# module.net
KiCad netlist of a schematic drawn in EAGLE
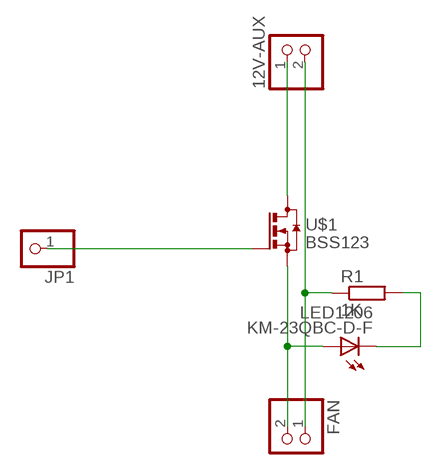
[diagram p0: schematic, sheet 1]

(export (version "E")
  (design (tool "Eeschema 10.0.6"))
  (components
    (comp (ref "12V-AUX")
      (value "PINHD-1X2")
      (footprint "eagle-import:1X02")
      (libsource (lib "eagle-import") (part "PINHD-1X2"))
    )
    (comp (ref "FAN")
      (value "PINHD-1X2")
      (footprint "eagle-import:1X02")
      (libsource (lib "eagle-import") (part "PINHD-1X2"))
    )
    (comp (ref "JP1")
      (value "PINHD-1X1")
      (footprint "eagle-import:1X01")
      (libsource (lib "eagle-import") (part "PINHD-1X1"))
    )
    (comp (ref "KM-23QBC-D-F")
      (value "LED1206")
      (footprint "eagle-import:LED1206")
      (libsource (lib "eagle-import") (part "LED1206"))
    )
    (comp (ref "R1")
      (value "1K")
      (footprint "eagle-import:R1206")
      (libsource (lib "eagle-import") (part "R-EU_R1206"))
    )
    (comp (ref "U$1")
      (value "BSS123")
      (footprint "eagle-import:SOT23")
      (libsource (lib "eagle-import") (part "BSS123"))
    )
  )
  (nets
    (net (code "1") (name "Net-(12V-AUX-Pad2)") (class "Default")
      (node (ref "12V-AUX") (pin "2") (pinfunction "2_2") (pintype "passive"))
      (node (ref "FAN") (pin "1") (pinfunction "1_1") (pintype "passive"))
      (node (ref "R1") (pin "1") (pinfunction "1_1") (pintype "passive"))
    )
    (net (code "2") (name "Net-(KM-23QBC-D-F-PadC)") (class "Default")
      (node (ref "KM-23QBC-D-F") (pin "C") (pinfunction "C_C") (pintype "passive"))
      (node (ref "R1") (pin "2") (pinfunction "2_2") (pintype "passive"))
    )
    (net (code "3") (name "Net-(U$1-D)") (class "Default")
      (node (ref "12V-AUX") (pin "1") (pinfunction "1_1") (pintype "passive"))
      (node (ref "U$1") (pin "3") (pinfunction "D_3") (pintype "passive"))
    )
    (net (code "4") (name "Net-(U$1-G)") (class "Default")
      (node (ref "JP1") (pin "1") (pinfunction "1_1") (pintype "passive"))
      (node (ref "U$1") (pin "1") (pinfunction "G_1") (pintype "passive"))
    )
    (net (code "5") (name "Net-(U$1-S)") (class "Default")
      (node (ref "FAN") (pin "2") (pinfunction "2_2") (pintype "passive"))
      (node (ref "KM-23QBC-D-F") (pin "A") (pinfunction "A_A") (pintype "passive"))
      (node (ref "U$1") (pin "2") (pinfunction "S_2") (pintype "passive"))
    )
  )
)
